# Sensors.net
KiCad netlist of a schematic drawn in Altium Designer
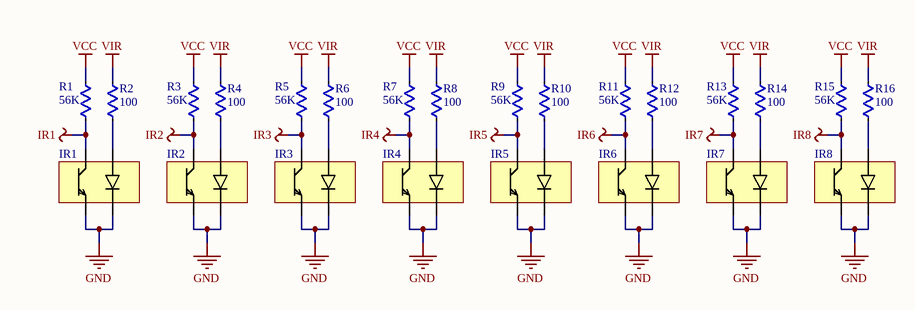
[diagram p0: Sensors.SchDoc]

(export (version "E")
  (design (tool "Eeschema 10.0.6"))
  (components
    (comp (ref "IR1")
      (value "QRE1113GR")
      (footprint "QRE1113GR")
      (fields (field (name "MF") "ON Semiconductor"))
      (libsource (lib "AltiumLibrary") (part "QRE1113GR"))
    )
    (comp (ref "IR2")
      (value "QRE1113GR")
      (footprint "QRE1113GR")
      (fields (field (name "MF") "ON Semiconductor"))
      (libsource (lib "AltiumLibrary") (part "QRE1113GR"))
    )
    (comp (ref "IR3")
      (value "QRE1113GR")
      (footprint "QRE1113GR")
      (fields (field (name "MF") "ON Semiconductor"))
      (libsource (lib "AltiumLibrary") (part "QRE1113GR"))
    )
    (comp (ref "IR4")
      (value "QRE1113GR")
      (footprint "QRE1113GR")
      (fields (field (name "MF") "ON Semiconductor"))
      (libsource (lib "AltiumLibrary") (part "QRE1113GR"))
    )
    (comp (ref "IR5")
      (value "QRE1113GR")
      (footprint "QRE1113GR")
      (fields (field (name "MF") "ON Semiconductor"))
      (libsource (lib "AltiumLibrary") (part "QRE1113GR"))
    )
    (comp (ref "IR6")
      (value "QRE1113GR")
      (footprint "QRE1113GR")
      (fields (field (name "MF") "ON Semiconductor"))
      (libsource (lib "AltiumLibrary") (part "QRE1113GR"))
    )
    (comp (ref "IR7")
      (value "QRE1113GR")
      (footprint "QRE1113GR")
      (fields (field (name "MF") "ON Semiconductor"))
      (libsource (lib "AltiumLibrary") (part "QRE1113GR"))
    )
    (comp (ref "IR8")
      (value "QRE1113GR")
      (footprint "QRE1113GR")
      (fields (field (name "MF") "ON Semiconductor"))
      (libsource (lib "AltiumLibrary") (part "QRE1113GR"))
    )
    (comp (ref "R1")
      (value "56K")
      (footprint "R1206")
      (fields (field (name "Comment") "RES"))
      (libsource (lib "AltiumLibrary") (part "RES"))
    )
    (comp (ref "R2")
      (value "100")
      (footprint "R1206")
      (fields (field (name "Comment") "RES"))
      (libsource (lib "AltiumLibrary") (part "RES"))
    )
    (comp (ref "R3")
      (value "56K")
      (footprint "R1206")
      (fields (field (name "Comment") "RES"))
      (libsource (lib "AltiumLibrary") (part "RES"))
    )
    (comp (ref "R4")
      (value "100")
      (footprint "R1206")
      (fields (field (name "Comment") "RES"))
      (libsource (lib "AltiumLibrary") (part "RES"))
    )
    (comp (ref "R5")
      (value "56K")
      (footprint "R1206")
      (fields (field (name "Comment") "RES"))
      (libsource (lib "AltiumLibrary") (part "RES"))
    )
    (comp (ref "R6")
      (value "100")
      (footprint "R1206")
      (fields (field (name "Comment") "RES"))
      (libsource (lib "AltiumLibrary") (part "RES"))
    )
    (comp (ref "R7")
      (value "56K")
      (footprint "R1206")
      (fields (field (name "Comment") "RES"))
      (libsource (lib "AltiumLibrary") (part "RES"))
    )
    (comp (ref "R8")
      (value "100")
      (footprint "R1206")
      (fields (field (name "Comment") "RES"))
      (libsource (lib "AltiumLibrary") (part "RES"))
    )
    (comp (ref "R9")
      (value "56K")
      (footprint "R1206")
      (fields (field (name "Comment") "RES"))
      (libsource (lib "AltiumLibrary") (part "RES"))
    )
    (comp (ref "R10")
      (value "100")
      (footprint "R1206")
      (fields (field (name "Comment") "RES"))
      (libsource (lib "AltiumLibrary") (part "RES"))
    )
    (comp (ref "R11")
      (value "56K")
      (footprint "R1206")
      (fields (field (name "Comment") "RES"))
      (libsource (lib "AltiumLibrary") (part "RES"))
    )
    (comp (ref "R12")
      (value "100")
      (footprint "R1206")
      (fields (field (name "Comment") "RES"))
      (libsource (lib "AltiumLibrary") (part "RES"))
    )
    (comp (ref "R13")
      (value "56K")
      (footprint "R1206")
      (fields (field (name "Comment") "RES"))
      (libsource (lib "AltiumLibrary") (part "RES"))
    )
    (comp (ref "R14")
      (value "100")
      (footprint "R1206")
      (fields (field (name "Comment") "RES"))
      (libsource (lib "AltiumLibrary") (part "RES"))
    )
    (comp (ref "R15")
      (value "56K")
      (footprint "R1206")
      (fields (field (name "Comment") "RES"))
      (libsource (lib "AltiumLibrary") (part "RES"))
    )
    (comp (ref "R16")
      (value "100")
      (footprint "R1206")
      (fields (field (name "Comment") "RES"))
      (libsource (lib "AltiumLibrary") (part "RES"))
    )
  )
  (nets
    (net (code "1") (name "GND") (class "Default")
      (node (ref "IR1") (pin "E") (pinfunction "E_E") (pintype "passive"))
      (node (ref "IR1") (pin "K") (pinfunction "K_K") (pintype "passive"))
      (node (ref "IR2") (pin "E") (pinfunction "E_E") (pintype "passive"))
      (node (ref "IR2") (pin "K") (pinfunction "K_K") (pintype "passive"))
      (node (ref "IR3") (pin "E") (pinfunction "E_E") (pintype "passive"))
      (node (ref "IR3") (pin "K") (pinfunction "K_K") (pintype "passive"))
      (node (ref "IR4") (pin "E") (pinfunction "E_E") (pintype "passive"))
      (node (ref "IR4") (pin "K") (pinfunction "K_K") (pintype "passive"))
      (node (ref "IR5") (pin "E") (pinfunction "E_E") (pintype "passive"))
      (node (ref "IR5") (pin "K") (pinfunction "K_K") (pintype "passive"))
      (node (ref "IR6") (pin "E") (pinfunction "E_E") (pintype "passive"))
      (node (ref "IR6") (pin "K") (pinfunction "K_K") (pintype "passive"))
      (node (ref "IR7") (pin "E") (pinfunction "E_E") (pintype "passive"))
      (node (ref "IR7") (pin "K") (pinfunction "K_K") (pintype "passive"))
      (node (ref "IR8") (pin "E") (pinfunction "E_E") (pintype "passive"))
      (node (ref "IR8") (pin "K") (pinfunction "K_K") (pintype "passive"))
    )
    (net (code "2") (name "IR1") (class "Default")
      (node (ref "IR1") (pin "C") (pinfunction "C_C") (pintype "passive"))
      (node (ref "R1") (pin "1") (pintype "passive"))
    )
    (net (code "3") (name "IR2") (class "Default")
      (node (ref "IR2") (pin "C") (pinfunction "C_C") (pintype "passive"))
      (node (ref "R3") (pin "1") (pintype "passive"))
    )
    (net (code "4") (name "IR3") (class "Default")
      (node (ref "IR3") (pin "C") (pinfunction "C_C") (pintype "passive"))
      (node (ref "R5") (pin "1") (pintype "passive"))
    )
    (net (code "5") (name "IR4") (class "Default")
      (node (ref "IR4") (pin "C") (pinfunction "C_C") (pintype "passive"))
      (node (ref "R7") (pin "1") (pintype "passive"))
    )
    (net (code "6") (name "IR5") (class "Default")
      (node (ref "IR5") (pin "C") (pinfunction "C_C") (pintype "passive"))
      (node (ref "R9") (pin "1") (pintype "passive"))
    )
    (net (code "7") (name "IR6") (class "Default")
      (node (ref "IR6") (pin "C") (pinfunction "C_C") (pintype "passive"))
      (node (ref "R11") (pin "1") (pintype "passive"))
    )
    (net (code "8") (name "IR7") (class "Default")
      (node (ref "IR7") (pin "C") (pinfunction "C_C") (pintype "passive"))
      (node (ref "R13") (pin "1") (pintype "passive"))
    )
    (net (code "9") (name "IR8") (class "Default")
      (node (ref "IR8") (pin "C") (pinfunction "C_C") (pintype "passive"))
      (node (ref "R15") (pin "1") (pintype "passive"))
    )
    (net (code "10") (name "Net-(IR1-PadA)") (class "Default")
      (node (ref "IR1") (pin "A") (pinfunction "A_A") (pintype "passive"))
      (node (ref "R2") (pin "1") (pintype "passive"))
    )
    (net (code "11") (name "Net-(IR2-PadA)") (class "Default")
      (node (ref "IR2") (pin "A") (pinfunction "A_A") (pintype "passive"))
      (node (ref "R4") (pin "1") (pintype "passive"))
    )
    (net (code "12") (name "Net-(IR3-PadA)") (class "Default")
      (node (ref "IR3") (pin "A") (pinfunction "A_A") (pintype "passive"))
      (node (ref "R6") (pin "1") (pintype "passive"))
    )
    (net (code "13") (name "Net-(IR4-PadA)") (class "Default")
      (node (ref "IR4") (pin "A") (pinfunction "A_A") (pintype "passive"))
      (node (ref "R8") (pin "1") (pintype "passive"))
    )
    (net (code "14") (name "Net-(IR5-PadA)") (class "Default")
      (node (ref "IR5") (pin "A") (pinfunction "A_A") (pintype "passive"))
      (node (ref "R10") (pin "1") (pintype "passive"))
    )
    (net (code "15") (name "Net-(IR6-PadA)") (class "Default")
      (node (ref "IR6") (pin "A") (pinfunction "A_A") (pintype "passive"))
      (node (ref "R12") (pin "1") (pintype "passive"))
    )
    (net (code "16") (name "Net-(IR7-PadA)") (class "Default")
      (node (ref "IR7") (pin "A") (pinfunction "A_A") (pintype "passive"))
      (node (ref "R14") (pin "1") (pintype "passive"))
    )
    (net (code "17") (name "Net-(IR8-PadA)") (class "Default")
      (node (ref "IR8") (pin "A") (pinfunction "A_A") (pintype "passive"))
      (node (ref "R16") (pin "1") (pintype "passive"))
    )
    (net (code "18") (name "VCC") (class "Default")
      (node (ref "R1") (pin "2") (pintype "passive"))
      (node (ref "R11") (pin "2") (pintype "passive"))
      (node (ref "R13") (pin "2") (pintype "passive"))
      (node (ref "R15") (pin "2") (pintype "passive"))
      (node (ref "R3") (pin "2") (pintype "passive"))
      (node (ref "R5") (pin "2") (pintype "passive"))
      (node (ref "R7") (pin "2") (pintype "passive"))
      (node (ref "R9") (pin "2") (pintype "passive"))
    )
    (net (code "19") (name "VIR") (class "Default")
      (node (ref "R10") (pin "2") (pintype "passive"))
      (node (ref "R12") (pin "2") (pintype "passive"))
      (node (ref "R14") (pin "2") (pintype "passive"))
      (node (ref "R16") (pin "2") (pintype "passive"))
      (node (ref "R2") (pin "2") (pintype "passive"))
      (node (ref "R4") (pin "2") (pintype "passive"))
      (node (ref "R6") (pin "2") (pintype "passive"))
      (node (ref "R8") (pin "2") (pintype "passive"))
    )
  )
)
